# TempAndHum.net
KiCad netlist of a schematic drawn in Altium Designer
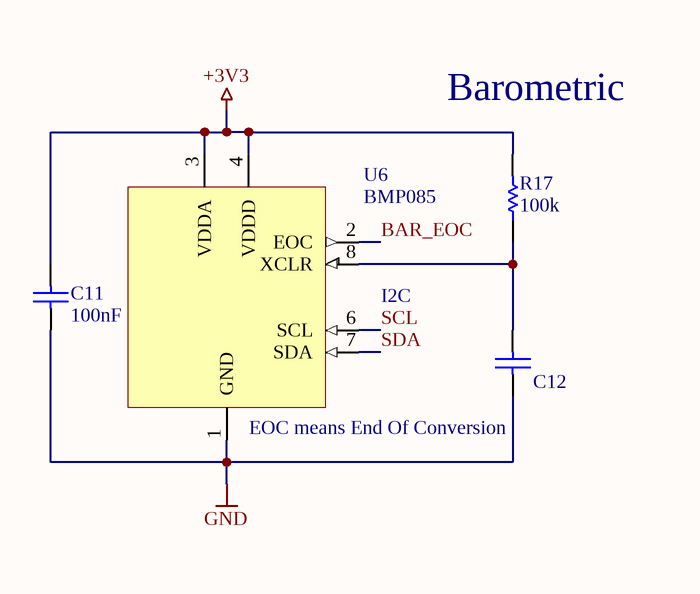
[diagram p0: TempAndHum.SchDoc]

(export (version "E")
  (design (tool "Eeschema 10.0.6"))
  (components
    (comp (ref "C11")
      (value "100nF")
      (footprint "CAPC0805(2012)100_M")
      (description "CAP 100nF 10V ±10% 0805 (2012 Metric) Thickness 1mm SMD")
      (fields (field (name "TOLERANCE") "±10%") (field (name "Comment") "CAP 100nF 10V 0805(2012)"))
      (libsource (lib "Altium Content Vault") (part "CMP-1036-04394-1"))
    )
    (comp (ref "C12")
      (value "CAP 10nF 10V 0805(2012)")
      (footprint "CAPC0805(2012)100_L")
      (description "CAP 10nF 10V ±10% 0805 (2012 Metric) Thickness 1mm SMD")
      (fields (field (name "TOLERANCE") "±10%"))
      (libsource (lib "Altium Content Vault") (part "CAP"))
    )
    (comp (ref "R17")
      (value "100k")
      (footprint "6-0805")
      (fields (field (name "PUBLISHER") "Altium Limited"))
      (libsource (lib "Panasonic Resistor") (part "ERJ6RB"))
    )
    (comp (ref "U6") (value "BMP085") (footprint "BMP085") (libsource (lib "auxcomp") (part "BMP085")))
  )
  (nets
    (net (code "1") (name "+3V3") (class "Default")
      (node (ref "C11") (pin "2") (pinfunction "2_2") (pintype "passive"))
      (node (ref "R17") (pin "2") (pinfunction "2_2") (pintype "passive"))
      (node (ref "U6") (pin "3") (pinfunction "VDDA_3") (pintype "power_in"))
      (node (ref "U6") (pin "4") (pinfunction "VDDD_4") (pintype "power_in"))
    )
    (net (code "2") (name "/BAR_EOC") (class "Default")
      (node (ref "U6") (pin "2") (pinfunction "EOC_2") (pintype "output"))
    )
    (net (code "3") (name "/SCL") (class "Default")
      (node (ref "U6") (pin "6") (pinfunction "SCL_6") (pintype "input"))
    )
    (net (code "4") (name "/SDA") (class "Default")
      (node (ref "U6") (pin "7") (pinfunction "SDA_7") (pintype "input"))
    )
    (net (code "5") (name "GND") (class "Default")
      (node (ref "C11") (pin "1") (pinfunction "1_1") (pintype "passive"))
      (node (ref "C12") (pin "1") (pinfunction "1_1") (pintype "passive"))
      (node (ref "U6") (pin "1") (pinfunction "GND_1") (pintype "power_in"))
    )
    (net (code "6") (name "Net-(U6-XCLR)") (class "Default")
      (node (ref "C12") (pin "2") (pinfunction "2_2") (pintype "passive"))
      (node (ref "R17") (pin "1") (pinfunction "1_1") (pintype "passive"))
      (node (ref "U6") (pin "8") (pinfunction "XCLR_8") (pintype "input"))
    )
  )
)
